# 02_Sensor.net
KiCad netlist of a schematic drawn in Altium Designer
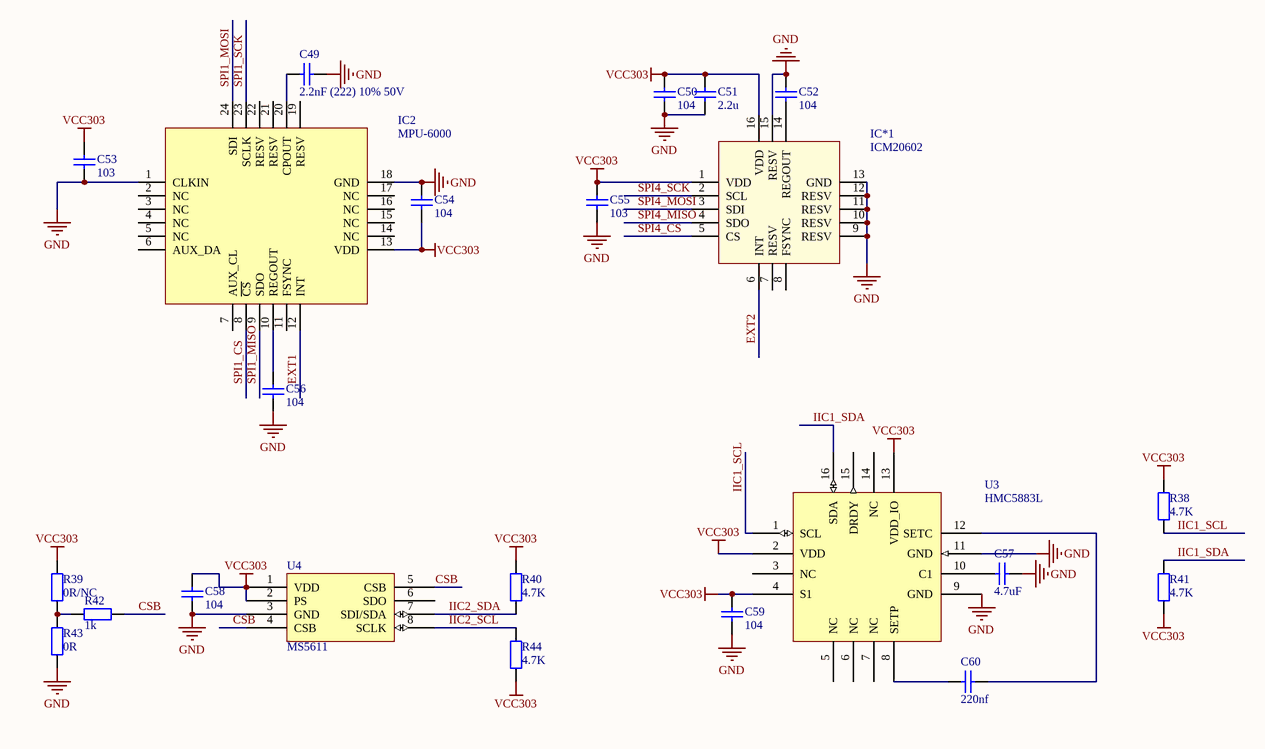
[diagram p0: 02_Sensor.SchDoc]

(export (version "E")
  (design (tool "Eeschema 10.0.6"))
  (components
    (comp (ref "C49")
      (value "2.2nF (222) 10% 50V")
      (footprint "LC-0402_C")
      (description "贴片电容")
      (libsource (lib "Miscellaneous Devices LC") (part "0603 2.2nF (222) 10% 50V"))
    )
    (comp (ref "C50")
      (value "104")
      (footprint "LC-0402_C")
      (description "贴片电容")
      (libsource (lib "Miscellaneous Devices LC") (part "0603 2.2nF (222) 10% 50V"))
    )
    (comp (ref "C51")
      (value "2.2u")
      (footprint "0603_C")
      (description "贴片电容")
      (libsource (lib "Miscellaneous Devices LC") (part "0603 2.2nF (222) 10% 50V"))
    )
    (comp (ref "C52")
      (value "104")
      (footprint "LC-0402_C")
      (description "贴片电容")
      (libsource (lib "Miscellaneous Devices LC") (part "0603 2.2nF (222) 10% 50V"))
    )
    (comp (ref "C53")
      (value "103")
      (footprint "LC-0402_C")
      (description "贴片电容")
      (libsource (lib "Miscellaneous Devices LC") (part "0603 2.2nF (222) 10% 50V"))
    )
    (comp (ref "C54")
      (value "104")
      (footprint "LC-0402_C")
      (description "贴片电容")
      (libsource (lib "Miscellaneous Devices LC") (part "0603 2.2nF (222) 10% 50V"))
    )
    (comp (ref "C55")
      (value "103")
      (footprint "LC-0402_C")
      (description "贴片电容")
      (libsource (lib "Miscellaneous Devices LC") (part "0603 2.2nF (222) 10% 50V"))
    )
    (comp (ref "C56")
      (value "104")
      (footprint "LC-0402_C")
      (description "贴片电容")
      (libsource (lib "Miscellaneous Devices LC") (part "0603 2.2nF (222) 10% 50V"))
    )
    (comp (ref "C57")
      (value "4.7uF")
      (footprint "0603_C")
      (description "贴片电容")
      (libsource (lib "Miscellaneous Devices LC") (part "0603 2.2nF (222) 10% 50V"))
    )
    (comp (ref "C58")
      (value "104")
      (footprint "LC-0402_C")
      (description "贴片电容")
      (libsource (lib "Miscellaneous Devices LC") (part "0603 2.2nF (222) 10% 50V"))
    )
    (comp (ref "C59")
      (value "104")
      (footprint "LC-0402_C")
      (description "贴片电容")
      (libsource (lib "Miscellaneous Devices LC") (part "0603 2.2nF (222) 10% 50V"))
    )
    (comp (ref "C60")
      (value "220nf")
      (footprint "LC-0402_C")
      (description "贴片电容")
      (libsource (lib "Miscellaneous Devices LC") (part "0603 2.2nF (222) 10% 50V"))
    )
    (comp (ref "IC*1")
      (value "ICM20602")
      (footprint "LGA16-icm20602")
      (libsource (lib "Schlib1") (part "ICM20602"))
    )
    (comp (ref "IC2")
      (value "MPU-6000")
      (footprint "MPU6000")
      (description "传感器")
      (libsource (lib "Schlib1") (part "MPU-6000"))
    )
    (comp (ref "R38")
      (value "4.7K")
      (footprint "LC-0402_R")
      (description "贴片电阻")
      (libsource (lib "Miscellaneous Devices LC") (part "0603 2.2KΩ (2201) 1%"))
    )
    (comp (ref "R39")
      (value "0R/NC")
      (footprint "LC-0402_R")
      (description "贴片电阻")
      (libsource (lib "Miscellaneous Devices LC") (part "0603 2.2KΩ (2201) 1%"))
    )
    (comp (ref "R40")
      (value "4.7K")
      (footprint "LC-0402_R")
      (description "贴片电阻")
      (libsource (lib "Miscellaneous Devices LC") (part "0603 2.2KΩ (2201) 1%"))
    )
    (comp (ref "R41")
      (value "4.7K")
      (footprint "LC-0402_R")
      (description "贴片电阻")
      (libsource (lib "Miscellaneous Devices LC") (part "0603 2.2KΩ (2201) 1%"))
    )
    (comp (ref "R42")
      (value "1k")
      (footprint "LC-0402_R")
      (description "贴片电阻")
      (libsource (lib "") (part "0603 2.2KΩ (2201) 1%_1"))
    )
    (comp (ref "R43")
      (value "0R")
      (footprint "LC-0402_R")
      (description "贴片电阻")
      (libsource (lib "Miscellaneous Devices LC") (part "0603 2.2KΩ (2201) 1%"))
    )
    (comp (ref "R44")
      (value "4.7K")
      (footprint "LC-0402_R")
      (description "贴片电阻")
      (libsource (lib "Miscellaneous Devices LC") (part "0603 2.2KΩ (2201) 1%"))
    )
    (comp (ref "U3")
      (value "HMC5883L")
      (footprint "Device:HMC5883L")
      (description "3-Axis Digital Compass")
      (libsource (lib "Device") (part "HMC5883L"))
    )
    (comp (ref "U4") (value "MS5611") (footprint "MS5611") (libsource (lib "Sensor") (part "MS5611")))
  )
  (nets
    (net (code "1") (name "/CSB") (class "Default")
      (node (ref "R42") (pin "2") (pinfunction "2_2") (pintype "passive"))
      (node (ref "U4") (pin "4") (pinfunction "CSB_4") (pintype "passive"))
      (node (ref "U4") (pin "5") (pinfunction "CSB_5") (pintype "passive"))
    )
    (net (code "2") (name "/EXT1") (class "Default")
      (node (ref "IC2") (pin "12") (pinfunction "INT_12") (pintype "passive"))
    )
    (net (code "3") (name "/EXT2") (class "Default")
      (node (ref "IC*1") (pin "6") (pinfunction "INT_6") (pintype "passive"))
    )
    (net (code "4") (name "/IIC1_SCL") (class "Default")
      (node (ref "R38") (pin "1") (pinfunction "1_1") (pintype "passive"))
      (node (ref "U3") (pin "1") (pinfunction "SCL_1") (pintype "bidirectional"))
    )
    (net (code "5") (name "/IIC1_SDA") (class "Default")
      (node (ref "R41") (pin "2") (pinfunction "2_2") (pintype "passive"))
      (node (ref "U3") (pin "16") (pinfunction "SDA_16") (pintype "bidirectional"))
    )
    (net (code "6") (name "/IIC2_SCL") (class "Default")
      (node (ref "R44") (pin "2") (pinfunction "2_2") (pintype "passive"))
      (node (ref "U4") (pin "8") (pinfunction "SCLK_8") (pintype "bidirectional"))
    )
    (net (code "7") (name "/IIC2_SDA") (class "Default")
      (node (ref "R40") (pin "1") (pinfunction "1_1") (pintype "passive"))
      (node (ref "U4") (pin "7") (pinfunction "SDI/SDA_7") (pintype "bidirectional"))
    )
    (net (code "8") (name "/SPI1_CS") (class "Default")
      (node (ref "IC2") (pin "8") (pinfunction "~{CS}_8") (pintype "passive"))
    )
    (net (code "9") (name "/SPI1_MISO") (class "Default")
      (node (ref "IC2") (pin "9") (pinfunction "SDO_9") (pintype "passive"))
    )
    (net (code "10") (name "/SPI1_MOSI") (class "Default")
      (node (ref "IC2") (pin "24") (pinfunction "SDI_24") (pintype "passive"))
    )
    (net (code "11") (name "/SPI1_SCK") (class "Default")
      (node (ref "IC2") (pin "23") (pinfunction "SCLK_23") (pintype "passive"))
    )
    (net (code "12") (name "/SPI4_CS") (class "Default")
      (node (ref "IC*1") (pin "5") (pinfunction "CS_5") (pintype "passive"))
    )
    (net (code "13") (name "/SPI4_MISO") (class "Default")
      (node (ref "IC*1") (pin "4") (pinfunction "SDO_4") (pintype "passive"))
    )
    (net (code "14") (name "/SPI4_MOSI") (class "Default")
      (node (ref "IC*1") (pin "3") (pinfunction "SDI_3") (pintype "passive"))
    )
    (net (code "15") (name "/SPI4_SCK") (class "Default")
      (node (ref "IC*1") (pin "2") (pinfunction "SCL_2") (pintype "passive"))
    )
    (net (code "16") (name "GND") (class "Default")
      (node (ref "C49") (pin "2") (pinfunction "2_2") (pintype "passive"))
      (node (ref "C50") (pin "1") (pinfunction "1_1") (pintype "passive"))
      (node (ref "C51") (pin "1") (pinfunction "1_1") (pintype "passive"))
      (node (ref "C52") (pin "2") (pinfunction "2_2") (pintype "passive"))
      (node (ref "C53") (pin "1") (pinfunction "1_1") (pintype "passive"))
      (node (ref "C54") (pin "2") (pinfunction "2_2") (pintype "passive"))
      (node (ref "C55") (pin "2") (pinfunction "2_2") (pintype "passive"))
      (node (ref "C56") (pin "1") (pinfunction "1_1") (pintype "passive"))
      (node (ref "C57") (pin "1") (pinfunction "1_1") (pintype "passive"))
      (node (ref "C58") (pin "1") (pinfunction "1_1") (pintype "passive"))
      (node (ref "C59") (pin "1") (pinfunction "1_1") (pintype "passive"))
      (node (ref "IC*1") (pin "10") (pinfunction "RESV_10") (pintype "passive"))
      (node (ref "IC*1") (pin "11") (pinfunction "RESV_11") (pintype "passive"))
      (node (ref "IC*1") (pin "12") (pinfunction "RESV_12") (pintype "passive"))
      (node (ref "IC*1") (pin "13") (pinfunction "GND_13") (pintype "passive"))
      (node (ref "IC*1") (pin "15") (pinfunction "RESV_15") (pintype "passive"))
      (node (ref "IC*1") (pin "9") (pinfunction "RESV_9") (pintype "passive"))
      (node (ref "IC2") (pin "1") (pinfunction "CLKIN_1") (pintype "passive"))
      (node (ref "IC2") (pin "18") (pinfunction "GND_18") (pintype "passive"))
      (node (ref "R43") (pin "1") (pinfunction "1_1") (pintype "passive"))
      (node (ref "U3") (pin "11") (pinfunction "GND_11") (pintype "input"))
      (node (ref "U3") (pin "9") (pinfunction "GND_9") (pintype "power_in"))
      (node (ref "U4") (pin "3") (pinfunction "GND_3") (pintype "passive"))
    )
    (net (code "17") (name "Net-(IC*1-REGOUT)") (class "Default")
      (node (ref "C52") (pin "1") (pinfunction "1_1") (pintype "passive"))
      (node (ref "IC*1") (pin "14") (pinfunction "REGOUT_14") (pintype "passive"))
    )
    (net (code "18") (name "Net-(IC2-CPOUT)") (class "Default")
      (node (ref "C49") (pin "1") (pinfunction "1_1") (pintype "passive"))
      (node (ref "IC2") (pin "20") (pinfunction "CPOUT_20") (pintype "passive"))
    )
    (net (code "19") (name "Net-(IC2-REGOUT)") (class "Default")
      (node (ref "C56") (pin "2") (pinfunction "2_2") (pintype "passive"))
      (node (ref "IC2") (pin "10") (pinfunction "REGOUT_10") (pintype "passive"))
    )
    (net (code "20") (name "Net-(R39-Pad1)") (class "Default")
      (node (ref "R39") (pin "1") (pinfunction "1_1") (pintype "passive"))
      (node (ref "R42") (pin "1") (pinfunction "1_1") (pintype "passive"))
      (node (ref "R43") (pin "2") (pinfunction "2_2") (pintype "passive"))
    )
    (net (code "21") (name "Net-(U3-C1)") (class "Default")
      (node (ref "C57") (pin "2") (pinfunction "2_2") (pintype "passive"))
      (node (ref "U3") (pin "10") (pinfunction "C1_10") (pintype "power_in"))
    )
    (net (code "22") (name "Net-(U3-SETC)") (class "Default")
      (node (ref "C60") (pin "1") (pinfunction "1_1") (pintype "passive"))
      (node (ref "U3") (pin "12") (pinfunction "SETC_12") (pintype "power_in"))
    )
    (net (code "23") (name "Net-(U3-SETP)") (class "Default")
      (node (ref "C60") (pin "2") (pinfunction "2_2") (pintype "passive"))
      (node (ref "U3") (pin "8") (pinfunction "SETP_8") (pintype "power_in"))
    )
    (net (code "24") (name "VCC303") (class "Default")
      (node (ref "C50") (pin "2") (pinfunction "2_2") (pintype "passive"))
      (node (ref "C51") (pin "2") (pinfunction "2_2") (pintype "passive"))
      (node (ref "C53") (pin "2") (pinfunction "2_2") (pintype "passive"))
      (node (ref "C54") (pin "1") (pinfunction "1_1") (pintype "passive"))
      (node (ref "C55") (pin "1") (pinfunction "1_1") (pintype "passive"))
      (node (ref "C58") (pin "2") (pinfunction "2_2") (pintype "passive"))
      (node (ref "C59") (pin "2") (pinfunction "2_2") (pintype "passive"))
      (node (ref "IC*1") (pin "1") (pinfunction "VDD_1") (pintype "passive"))
      (node (ref "IC*1") (pin "16") (pinfunction "VDD_16") (pintype "passive"))
      (node (ref "IC2") (pin "13") (pinfunction "VDD_13") (pintype "passive"))
      (node (ref "R38") (pin "2") (pinfunction "2_2") (pintype "passive"))
      (node (ref "R39") (pin "2") (pinfunction "2_2") (pintype "passive"))
      (node (ref "R40") (pin "2") (pinfunction "2_2") (pintype "passive"))
      (node (ref "R41") (pin "1") (pinfunction "1_1") (pintype "passive"))
      (node (ref "R44") (pin "1") (pinfunction "1_1") (pintype "passive"))
      (node (ref "U3") (pin "13") (pinfunction "VDD_IO_13") (pintype "power_in"))
      (node (ref "U3") (pin "2") (pinfunction "VDD_2") (pintype "power_in"))
      (node (ref "U3") (pin "4") (pinfunction "S1_4") (pintype "power_in"))
      (node (ref "U4") (pin "1") (pinfunction "VDD_1") (pintype "passive"))
      (node (ref "U4") (pin "2") (pinfunction "PS_2") (pintype "passive"))
    )
    (net (code "25") (name "unconnected-(IC*1-FSYNC-Pad8)") (class "Default")
      (node (ref "IC*1") (pin "8") (pinfunction "FSYNC_8") (pintype "passive"))
    )
    (net (code "26") (name "unconnected-(IC*1-RESV-Pad7)") (class "Default")
      (node (ref "IC*1") (pin "7") (pinfunction "RESV_7") (pintype "passive"))
    )
    (net (code "27") (name "unconnected-(IC2-AUX_CL-Pad7)") (class "Default")
      (node (ref "IC2") (pin "7") (pinfunction "AUX_CL_7") (pintype "passive"))
    )
    (net (code "28") (name "unconnected-(IC2-AUX_DA-Pad6)") (class "Default")
      (node (ref "IC2") (pin "6") (pinfunction "AUX_DA_6") (pintype "passive"))
    )
    (net (code "29") (name "unconnected-(IC2-FSYNC-Pad11)") (class "Default")
      (node (ref "IC2") (pin "11") (pinfunction "FSYNC_11") (pintype "passive"))
    )
    (net (code "30") (name "unconnected-(IC2-NC-Pad2)") (class "Default")
      (node (ref "IC2") (pin "2") (pinfunction "NC_2") (pintype "passive"))
    )
    (net (code "31") (name "unconnected-(IC2-NC-Pad3)") (class "Default")
      (node (ref "IC2") (pin "3") (pinfunction "NC_3") (pintype "passive"))
    )
    (net (code "32") (name "unconnected-(IC2-NC-Pad4)") (class "Default")
      (node (ref "IC2") (pin "4") (pinfunction "NC_4") (pintype "passive"))
    )
    (net (code "33") (name "unconnected-(IC2-NC-Pad5)") (class "Default")
      (node (ref "IC2") (pin "5") (pinfunction "NC_5") (pintype "passive"))
    )
    (net (code "34") (name "unconnected-(IC2-NC-Pad14)") (class "Default")
      (node (ref "IC2") (pin "14") (pinfunction "NC_14") (pintype "passive"))
    )
    (net (code "35") (name "unconnected-(IC2-NC-Pad15)") (class "Default")
      (node (ref "IC2") (pin "15") (pinfunction "NC_15") (pintype "passive"))
    )
    (net (code "36") (name "unconnected-(IC2-NC-Pad16)") (class "Default")
      (node (ref "IC2") (pin "16") (pinfunction "NC_16") (pintype "passive"))
    )
    (net (code "37") (name "unconnected-(IC2-NC-Pad17)") (class "Default")
      (node (ref "IC2") (pin "17") (pinfunction "NC_17") (pintype "passive"))
    )
    (net (code "38") (name "unconnected-(IC2-RESV-Pad19)") (class "Default")
      (node (ref "IC2") (pin "19") (pinfunction "RESV_19") (pintype "passive"))
    )
    (net (code "39") (name "unconnected-(IC2-RESV-Pad21)") (class "Default")
      (node (ref "IC2") (pin "21") (pinfunction "RESV_21") (pintype "passive"))
    )
    (net (code "40") (name "unconnected-(IC2-RESV-Pad22)") (class "Default")
      (node (ref "IC2") (pin "22") (pinfunction "RESV_22") (pintype "passive"))
    )
    (net (code "41") (name "unconnected-(U3-DRDY-Pad15)") (class "Default")
      (node (ref "U3") (pin "15") (pinfunction "DRDY_15") (pintype "output"))
    )
    (net (code "42") (name "unconnected-(U3-NC-Pad3)") (class "Default")
      (node (ref "U3") (pin "3") (pinfunction "NC_3") (pintype "passive"))
    )
    (net (code "43") (name "unconnected-(U3-NC-Pad5)") (class "Default")
      (node (ref "U3") (pin "5") (pinfunction "NC_5") (pintype "passive"))
    )
    (net (code "44") (name "unconnected-(U3-NC-Pad6)") (class "Default")
      (node (ref "U3") (pin "6") (pinfunction "NC_6") (pintype "passive"))
    )
    (net (code "45") (name "unconnected-(U3-NC-Pad7)") (class "Default")
      (node (ref "U3") (pin "7") (pinfunction "NC_7") (pintype "passive"))
    )
    (net (code "46") (name "unconnected-(U3-NC-Pad14)") (class "Default")
      (node (ref "U3") (pin "14") (pinfunction "NC_14") (pintype "passive"))
    )
    (net (code "47") (name "unconnected-(U4-SDO-Pad6)") (class "Default")
      (node (ref "U4") (pin "6") (pinfunction "SDO_6") (pintype "passive"))
    )
  )
)
